# expander8.net
KiCad netlist of a schematic drawn in EAGLE
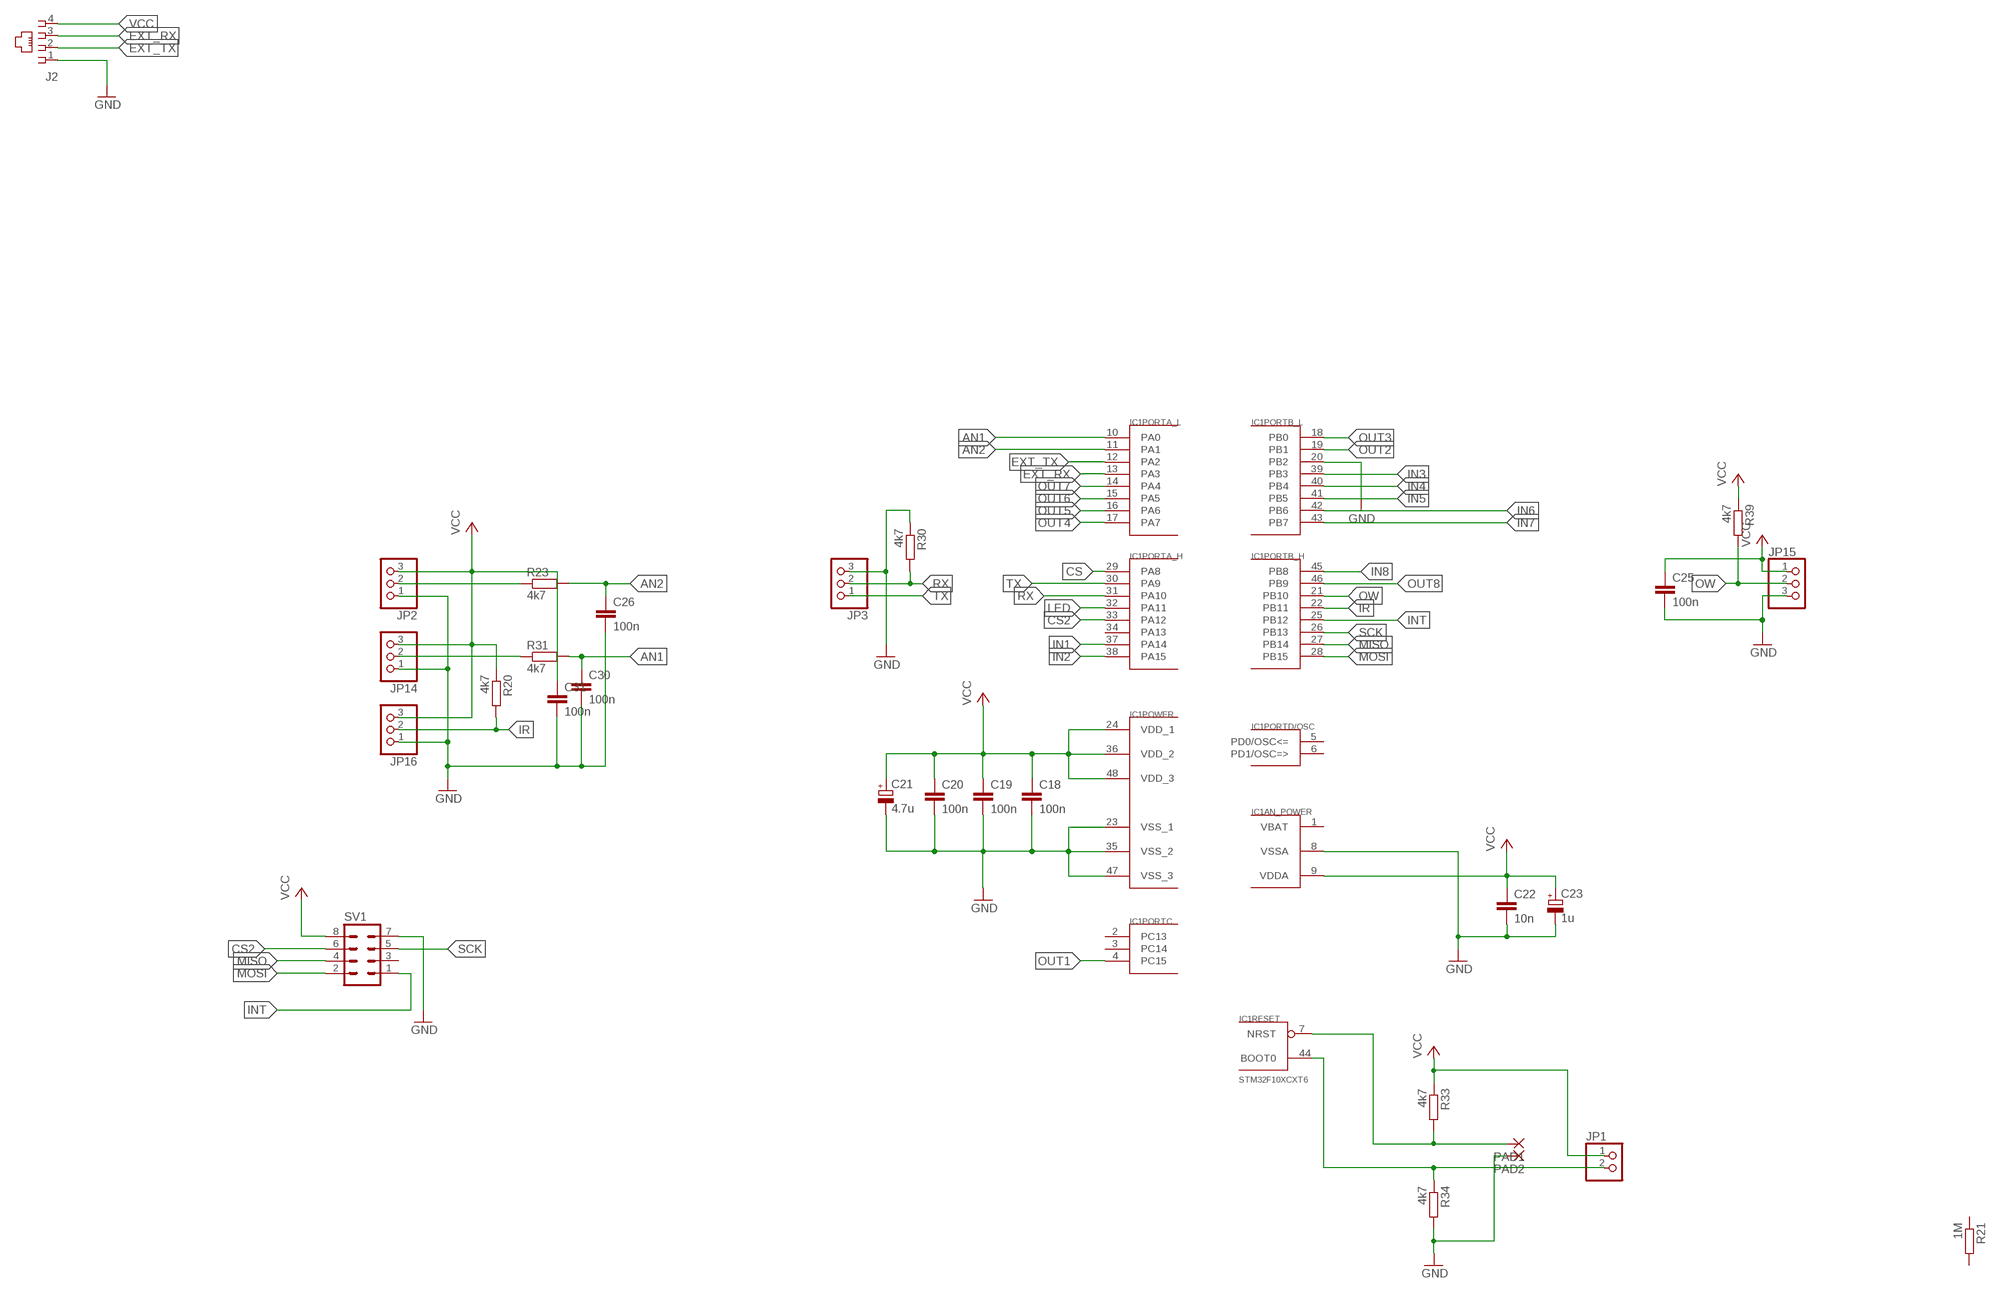
[diagram p0: schematic, sheet 1, part 1 of 3]
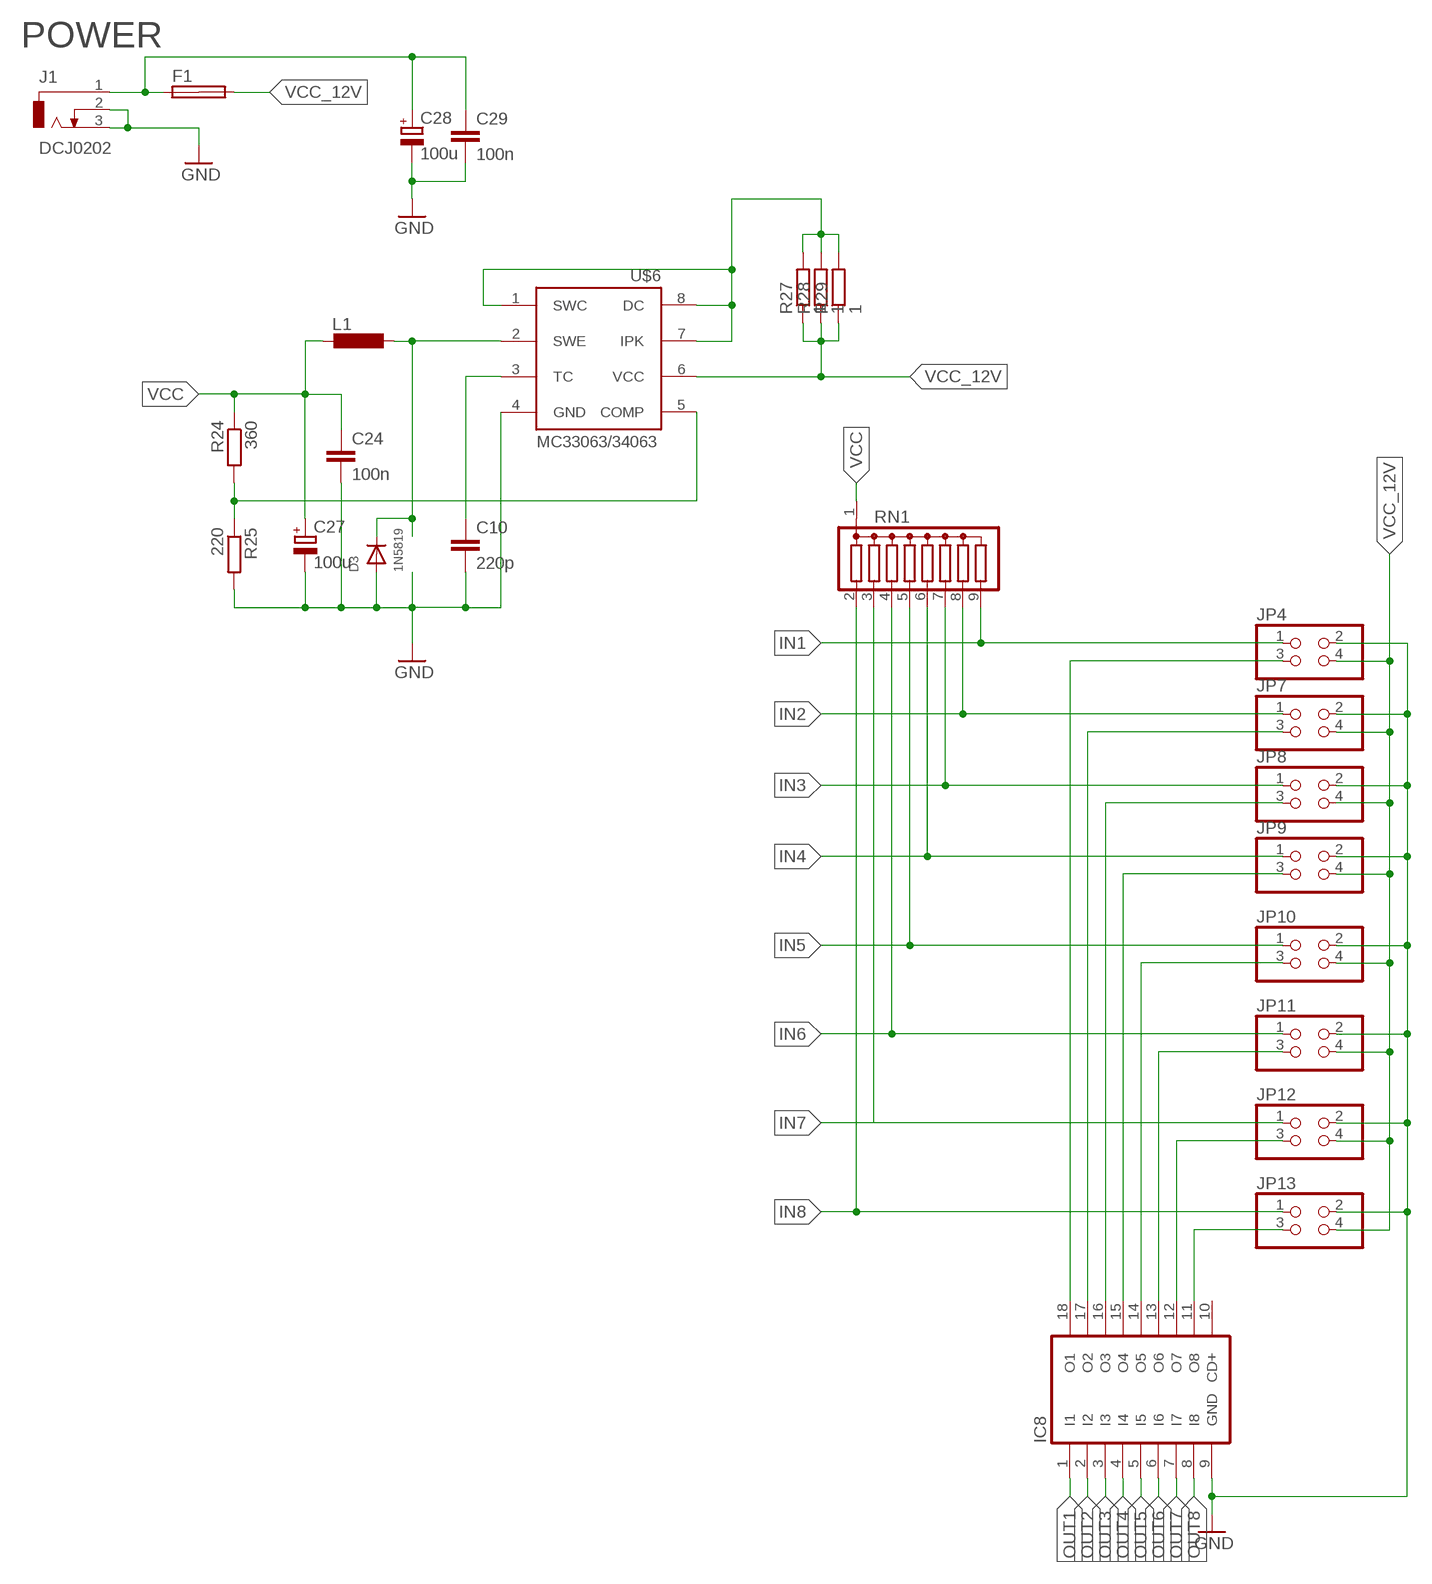
[diagram p1: schematic, sheet 1, part 2 of 3]
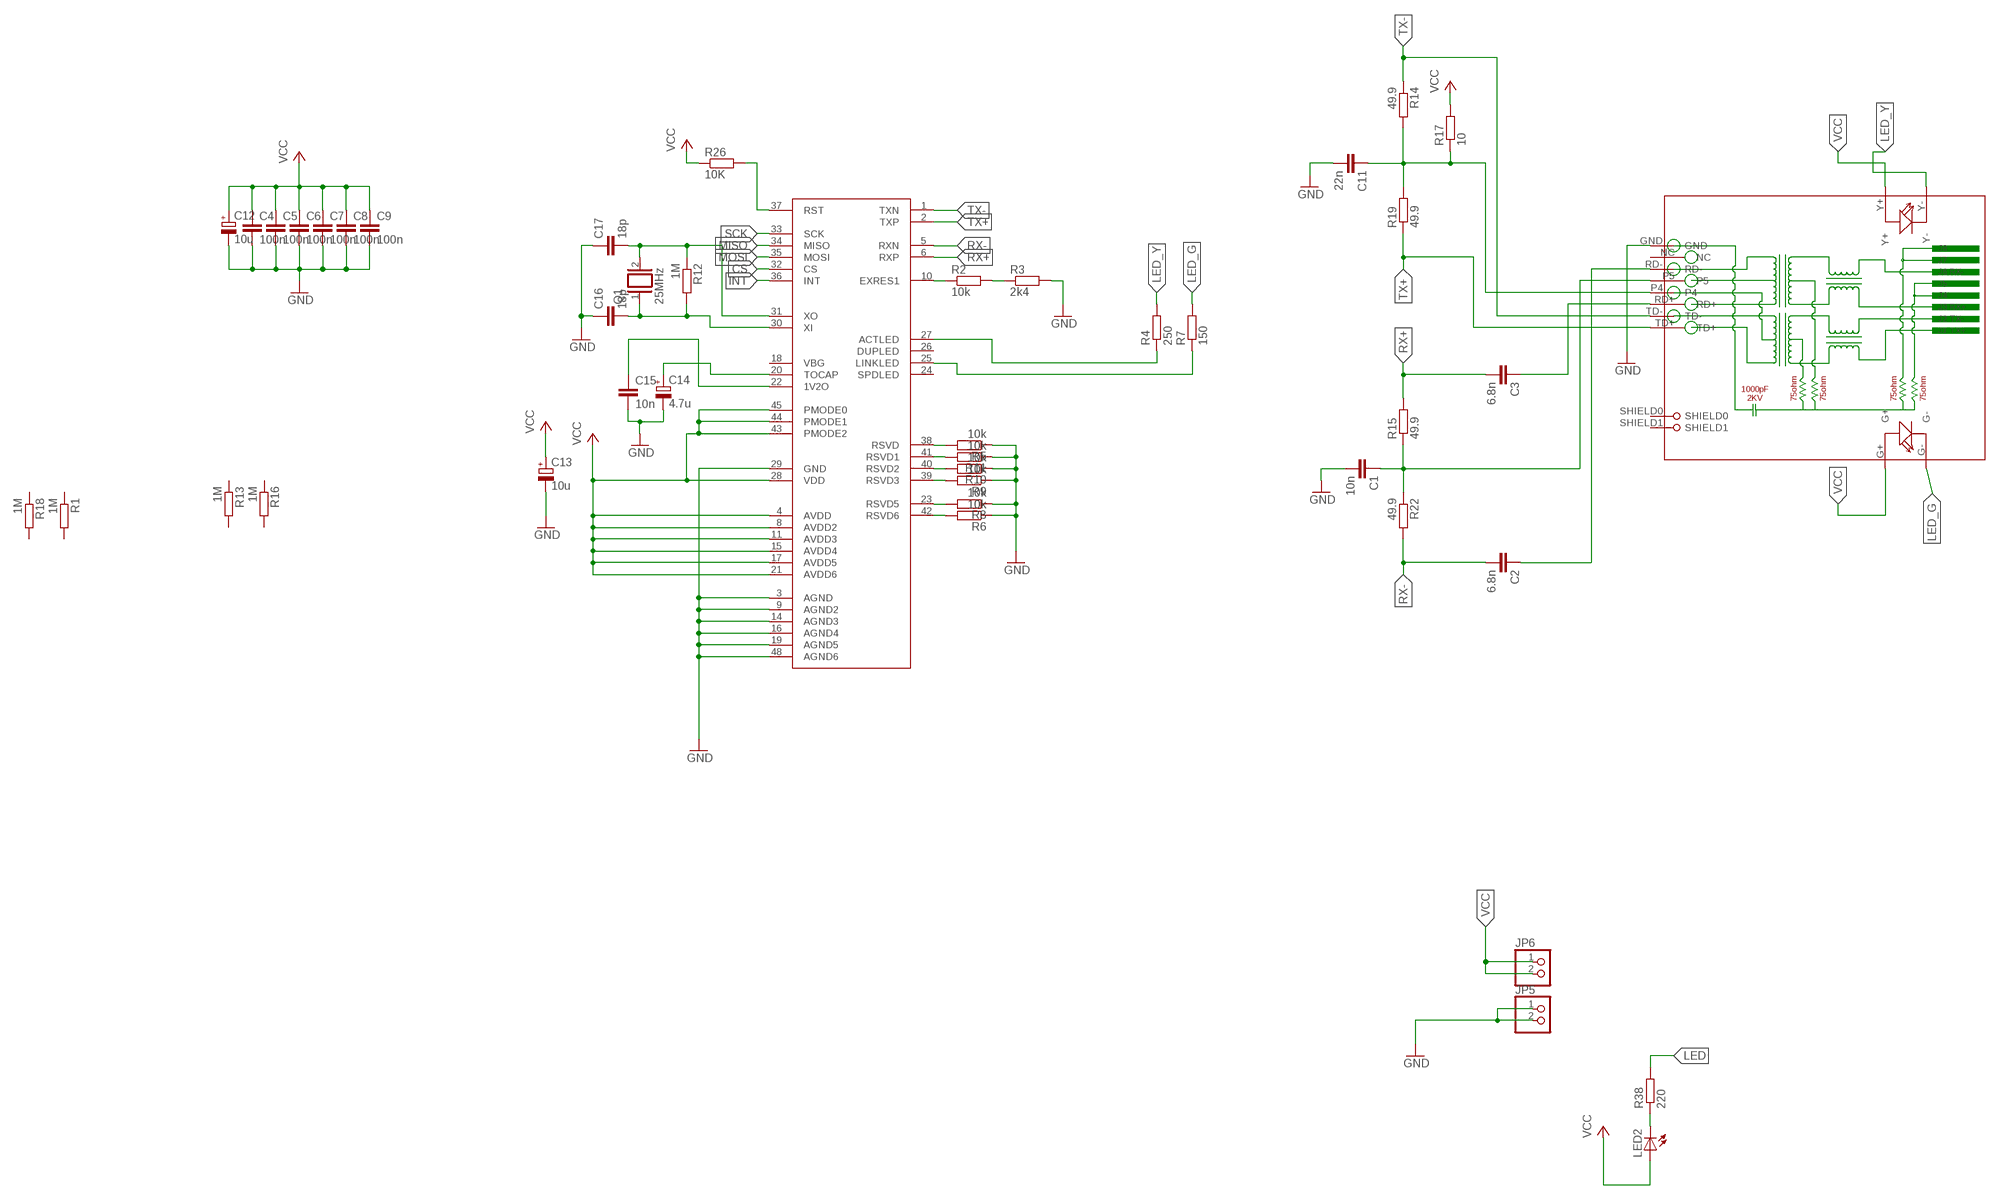
[diagram p2: schematic, sheet 1, part 3 of 3]

(export (version "E")
  (design (tool "Eeschema 10.0.6"))
  (components
    (comp (ref "C1")
      (value "10n")
      (footprint "eagle-import:C0805")
      (libsource (lib "eagle-import") (part "resistor_C-EUC0805"))
    )
    (comp (ref "C2")
      (value "6.8n")
      (footprint "eagle-import:C0805")
      (libsource (lib "eagle-import") (part "resistor_C-EUC0805"))
    )
    (comp (ref "C3")
      (value "6.8n")
      (footprint "eagle-import:C0805")
      (libsource (lib "eagle-import") (part "resistor_C-EUC0805"))
    )
    (comp (ref "C4")
      (value "100n")
      (footprint "eagle-import:C0805")
      (libsource (lib "eagle-import") (part "C-EUC0805"))
    )
    (comp (ref "C5")
      (value "100n")
      (footprint "eagle-import:C0805")
      (libsource (lib "eagle-import") (part "C-EUC0805"))
    )
    (comp (ref "C6")
      (value "100n")
      (footprint "eagle-import:C0805")
      (libsource (lib "eagle-import") (part "C-EUC0805"))
    )
    (comp (ref "C7")
      (value "100n")
      (footprint "eagle-import:C0805")
      (libsource (lib "eagle-import") (part "C-EUC0805"))
    )
    (comp (ref "C8")
      (value "100n")
      (footprint "eagle-import:C0805")
      (libsource (lib "eagle-import") (part "C-EUC0805"))
    )
    (comp (ref "C9")
      (value "100n")
      (footprint "eagle-import:C0805")
      (libsource (lib "eagle-import") (part "C-EUC0805"))
    )
    (comp (ref "C10")
      (value "220p")
      (footprint "eagle-import:C0805")
      (libsource (lib "eagle-import") (part "C-EUC0805"))
    )
    (comp (ref "C11")
      (value "22n")
      (footprint "eagle-import:C0805")
      (libsource (lib "eagle-import") (part "resistor_C-EUC0805"))
    )
    (comp (ref "C12")
      (value "10u")
      (footprint "eagle-import:E2,5-5")
      (libsource (lib "eagle-import") (part "CPOL-EUE2.5-5"))
    )
    (comp (ref "C13")
      (value "10u")
      (footprint "eagle-import:E2,5-5")
      (libsource (lib "eagle-import") (part "CPOL-EUE2.5-5"))
    )
    (comp (ref "C14")
      (value "4.7u")
      (footprint "eagle-import:E2,5-5")
      (libsource (lib "eagle-import") (part "CPOL-EUE2.5-5"))
    )
    (comp (ref "C15")
      (value "10n")
      (footprint "eagle-import:C1206")
      (libsource (lib "eagle-import") (part "C-EUC1206"))
    )
    (comp (ref "C16")
      (value "18p")
      (footprint "eagle-import:C0805")
      (libsource (lib "eagle-import") (part "C-EUC0805"))
    )
    (comp (ref "C17")
      (value "18p")
      (footprint "eagle-import:C0805")
      (libsource (lib "eagle-import") (part "C-EUC0805"))
    )
    (comp (ref "C18")
      (value "100n")
      (footprint "eagle-import:C0805")
      (libsource (lib "eagle-import") (part "C-EUC0805"))
    )
    (comp (ref "C19")
      (value "100n")
      (footprint "eagle-import:C0805")
      (libsource (lib "eagle-import") (part "C-EUC0805"))
    )
    (comp (ref "C20")
      (value "100n")
      (footprint "eagle-import:C0805")
      (libsource (lib "eagle-import") (part "C-EUC0805"))
    )
    (comp (ref "C21")
      (value "4.7u")
      (footprint "eagle-import:E2,5-5")
      (libsource (lib "eagle-import") (part "CPOL-EUE2.5-5"))
    )
    (comp (ref "C22")
      (value "10n")
      (footprint "eagle-import:C0805")
      (libsource (lib "eagle-import") (part "C-EUC0805"))
    )
    (comp (ref "C23")
      (value "1u")
      (footprint "eagle-import:E2,5-5")
      (libsource (lib "eagle-import") (part "CPOL-EUE2.5-5"))
    )
    (comp (ref "C24")
      (value "100n")
      (footprint "eagle-import:C0805")
      (libsource (lib "eagle-import") (part "C-EUC0805"))
    )
    (comp (ref "C25")
      (value "100n")
      (footprint "eagle-import:C1206")
      (libsource (lib "eagle-import") (part "resistor_C-EUC1206"))
    )
    (comp (ref "C26")
      (value "100n")
      (footprint "eagle-import:C0805")
      (libsource (lib "eagle-import") (part "C-EUC0805"))
    )
    (comp (ref "C27")
      (value "100u")
      (footprint "eagle-import:E2,5-7")
      (libsource (lib "eagle-import") (part "CPOL-EUE2.5-7"))
    )
    (comp (ref "C28")
      (value "100u")
      (footprint "eagle-import:E2,5-7")
      (libsource (lib "eagle-import") (part "CPOL-EUE2.5-7"))
    )
    (comp (ref "C29")
      (value "100n")
      (footprint "eagle-import:C0805")
      (libsource (lib "eagle-import") (part "C-EUC0805"))
    )
    (comp (ref "C30")
      (value "100n")
      (footprint "eagle-import:C1206")
      (libsource (lib "eagle-import") (part "C-EUC1206"))
    )
    (comp (ref "C31")
      (value "100n")
      (footprint "eagle-import:C0805")
      (libsource (lib "eagle-import") (part "C-EUC0805"))
    )
    (comp (ref "D3")
      (value "1N5819")
      (footprint "eagle-import:SMADIODE")
      (libsource (lib "eagle-import") (part "DIODESMA"))
    )
    (comp (ref "F1")
      (value "SHK20L")
      (footprint "eagle-import:SHK20L")
      (libsource (lib "eagle-import") (part "SHK20L"))
    )
    (comp (ref "IC1")
      (value "STM32F10XCXT6")
      (footprint "eagle-import:TQFP48")
      (libsource (lib "eagle-import") (part "STM32F10XCXT6"))
    )
    (comp (ref "IC8")
      (value "ULN2803AD")
      (footprint "eagle-import:SO18W")
      (libsource (lib "eagle-import") (part "ULN2803AD"))
    )
    (comp (ref "J1")
      (value "DCJ0202")
      (footprint "eagle-import:DCJ0202")
      (libsource (lib "eagle-import") (part "DCJ0202"))
    )
    (comp (ref "J2")
      (value "520250-2")
      (footprint "eagle-import:520250-2")
      (libsource (lib "eagle-import") (part "520250-2"))
    )
    (comp (ref "JP1")
      (value "PINHD-1X2")
      (footprint "eagle-import:1X02")
      (libsource (lib "eagle-import") (part "PINHD-1X2"))
    )
    (comp (ref "JP2")
      (value "PINHD-1X3")
      (footprint "eagle-import:1X03")
      (libsource (lib "eagle-import") (part "PINHD-1X3"))
    )
    (comp (ref "JP3")
      (value "PINHD-1X3")
      (footprint "eagle-import:1X03")
      (libsource (lib "eagle-import") (part "PINHD-1X3"))
    )
    (comp (ref "JP4")
      (value "PINHD-2X2/90")
      (footprint "eagle-import:2X02_90")
      (libsource (lib "eagle-import") (part "PINHD-2X2/90"))
    )
    (comp (ref "JP5")
      (value "PINHD-1X2")
      (footprint "eagle-import:1X02")
      (libsource (lib "eagle-import") (part "PINHD-1X2"))
    )
    (comp (ref "JP6")
      (value "PINHD-1X2")
      (footprint "eagle-import:1X02")
      (libsource (lib "eagle-import") (part "PINHD-1X2"))
    )
    (comp (ref "JP7")
      (value "PINHD-2X2/90")
      (footprint "eagle-import:2X02_90")
      (libsource (lib "eagle-import") (part "PINHD-2X2/90"))
    )
    (comp (ref "JP8")
      (value "PINHD-2X2/90")
      (footprint "eagle-import:2X02_90")
      (libsource (lib "eagle-import") (part "PINHD-2X2/90"))
    )
    (comp (ref "JP9")
      (value "PINHD-2X2/90")
      (footprint "eagle-import:2X02_90")
      (libsource (lib "eagle-import") (part "PINHD-2X2/90"))
    )
    (comp (ref "JP10")
      (value "PINHD-2X2/90")
      (footprint "eagle-import:2X02_90")
      (libsource (lib "eagle-import") (part "PINHD-2X2/90"))
    )
    (comp (ref "JP11")
      (value "PINHD-2X2/90")
      (footprint "eagle-import:2X02_90")
      (libsource (lib "eagle-import") (part "PINHD-2X2/90"))
    )
    (comp (ref "JP12")
      (value "PINHD-2X2/90")
      (footprint "eagle-import:2X02_90")
      (libsource (lib "eagle-import") (part "PINHD-2X2/90"))
    )
    (comp (ref "JP13")
      (value "PINHD-2X2/90")
      (footprint "eagle-import:2X02_90")
      (libsource (lib "eagle-import") (part "PINHD-2X2/90"))
    )
    (comp (ref "JP14")
      (value "PINHD-1X3")
      (footprint "eagle-import:1X03")
      (libsource (lib "eagle-import") (part "PINHD-1X3"))
    )
    (comp (ref "JP15")
      (value "PINHD-1X3")
      (footprint "eagle-import:1X03")
      (libsource (lib "eagle-import") (part "PINHD-1X3"))
    )
    (comp (ref "JP16")
      (value "PINHD-1X3")
      (footprint "eagle-import:1X03")
      (libsource (lib "eagle-import") (part "PINHD-1X3"))
    )
    (comp (ref "L1")
      (value "L-EU0207/2V")
      (footprint "eagle-import:0207_2V")
      (libsource (lib "eagle-import") (part "L-EU0207/2V"))
    )
    (comp (ref "LED2")
      (value "LEDCHIPLED_0805")
      (footprint "eagle-import:CHIPLED_0805")
      (libsource (lib "eagle-import") (part "LEDCHIPLED_0805"))
    )
    (comp (ref "PAD1")
      (value "SMD2")
      (footprint "eagle-import:SMD1,27-2,54")
      (libsource (lib "eagle-import") (part "SMD2"))
    )
    (comp (ref "PAD2")
      (value "SMD2")
      (footprint "eagle-import:SMD1,27-2,54")
      (libsource (lib "eagle-import") (part "SMD2"))
    )
    (comp (ref "Q1")
      (value "25MHz")
      (footprint "eagle-import:QS")
      (libsource (lib "eagle-import") (part "XTAL/S"))
    )
    (comp (ref "R1")
      (value "1M")
      (footprint "eagle-import:R1206")
      (libsource (lib "eagle-import") (part "rcl-kd_R-EU_R1206"))
    )
    (comp (ref "R2")
      (value "10k")
      (footprint "eagle-import:R0805")
      (libsource (lib "eagle-import") (part "rcl-kd_R-EU_R0805"))
    )
    (comp (ref "R3")
      (value "2k4")
      (footprint "eagle-import:R0805")
      (libsource (lib "eagle-import") (part "rcl-kd_R-EU_R0805"))
    )
    (comp (ref "R4")
      (value "250")
      (footprint "eagle-import:R1206")
      (libsource (lib "eagle-import") (part "rcl-kd_R-EU_R1206"))
    )
    (comp (ref "R5")
      (value "10k")
      (footprint "eagle-import:R0603")
      (libsource (lib "eagle-import") (part "rcl-kd_R-EU_R0603"))
    )
    (comp (ref "R6")
      (value "10k")
      (footprint "eagle-import:R0603")
      (libsource (lib "eagle-import") (part "rcl-kd_R-EU_R0603"))
    )
    (comp (ref "R7")
      (value "150")
      (footprint "eagle-import:R1206")
      (libsource (lib "eagle-import") (part "rcl-kd_R-EU_R1206"))
    )
    (comp (ref "R8")
      (value "10k")
      (footprint "eagle-import:R0805")
      (libsource (lib "eagle-import") (part "rcl-kd_R-EU_R0805"))
    )
    (comp (ref "R9")
      (value "10k")
      (footprint "eagle-import:R0603")
      (libsource (lib "eagle-import") (part "rcl-kd_R-EU_R0603"))
    )
    (comp (ref "R10")
      (value "10k")
      (footprint "eagle-import:R0603")
      (libsource (lib "eagle-import") (part "rcl-kd_R-EU_R0603"))
    )
    (comp (ref "R11")
      (value "10k")
      (footprint "eagle-import:R0603")
      (libsource (lib "eagle-import") (part "rcl-kd_R-EU_R0603"))
    )
    (comp (ref "R12")
      (value "1M")
      (footprint "eagle-import:R0805")
      (libsource (lib "eagle-import") (part "rcl-kd_R-EU_R0805"))
    )
    (comp (ref "R13")
      (value "1M")
      (footprint "eagle-import:R1206")
      (libsource (lib "eagle-import") (part "rcl-kd_R-EU_R1206"))
    )
    (comp (ref "R14")
      (value "49.9")
      (footprint "eagle-import:R0805")
      (libsource (lib "eagle-import") (part "resistor_R-EU_R0805"))
    )
    (comp (ref "R15")
      (value "49.9")
      (footprint "eagle-import:R1206")
      (libsource (lib "eagle-import") (part "resistor_R-EU_R1206"))
    )
    (comp (ref "R16")
      (value "1M")
      (footprint "eagle-import:R1206")
      (libsource (lib "eagle-import") (part "rcl-kd_R-EU_R1206"))
    )
    (comp (ref "R17")
      (value "10")
      (footprint "eagle-import:R0805")
      (libsource (lib "eagle-import") (part "resistor_R-EU_R0805"))
    )
    (comp (ref "R18")
      (value "1M")
      (footprint "eagle-import:R1206")
      (libsource (lib "eagle-import") (part "rcl-kd_R-EU_R1206"))
    )
    (comp (ref "R19")
      (value "49.9")
      (footprint "eagle-import:R1206")
      (libsource (lib "eagle-import") (part "resistor_R-EU_R1206"))
    )
    (comp (ref "R20")
      (value "4k7")
      (footprint "eagle-import:R0805")
      (libsource (lib "eagle-import") (part "resistor_R-EU_R0805"))
    )
    (comp (ref "R21")
      (value "1M")
      (footprint "eagle-import:R1206")
      (libsource (lib "eagle-import") (part "rcl-kd_R-EU_R1206"))
    )
    (comp (ref "R22")
      (value "49.9")
      (footprint "eagle-import:R0805")
      (libsource (lib "eagle-import") (part "resistor_R-EU_R0805"))
    )
    (comp (ref "R23")
      (value "4k7")
      (footprint "eagle-import:R0805")
      (libsource (lib "eagle-import") (part "resistor_R-EU_R0805"))
    )
    (comp (ref "R24")
      (value "360")
      (footprint "eagle-import:M1206")
      (libsource (lib "eagle-import") (part "R-EU_M1206"))
    )
    (comp (ref "R25")
      (value "220")
      (footprint "eagle-import:M1206")
      (libsource (lib "eagle-import") (part "R-EU_M1206"))
    )
    (comp (ref "R26")
      (value "10K")
      (footprint "eagle-import:R0805")
      (libsource (lib "eagle-import") (part "rcl-kd_R-EU_R0805"))
    )
    (comp (ref "R27")
      (value "1")
      (footprint "eagle-import:R1206")
      (libsource (lib "eagle-import") (part "rcl-kd_R-EU_R1206"))
    )
    (comp (ref "R28")
      (value "1")
      (footprint "eagle-import:R1206")
      (libsource (lib "eagle-import") (part "rcl-kd_R-EU_R1206"))
    )
    (comp (ref "R29")
      (value "1")
      (footprint "eagle-import:R1206")
      (libsource (lib "eagle-import") (part "rcl-kd_R-EU_R1206"))
    )
    (comp (ref "R30")
      (value "4k7")
      (footprint "eagle-import:R1206")
      (libsource (lib "eagle-import") (part "resistor_R-EU_R1206"))
    )
    (comp (ref "R31")
      (value "4k7")
      (footprint "eagle-import:R0805")
      (libsource (lib "eagle-import") (part "resistor_R-EU_R0805"))
    )
    (comp (ref "R33")
      (value "4k7")
      (footprint "eagle-import:R0805")
      (libsource (lib "eagle-import") (part "rcl-kd_R-EU_R0805"))
    )
    (comp (ref "R34")
      (value "4k7")
      (footprint "eagle-import:R1206")
      (libsource (lib "eagle-import") (part "rcl-kd_R-EU_R1206"))
    )
    (comp (ref "R38")
      (value "220")
      (footprint "eagle-import:R0805")
      (libsource (lib "eagle-import") (part "resistor_R-EU_R0805"))
    )
    (comp (ref "R39")
      (value "4k7")
      (footprint "eagle-import:R0805")
      (libsource (lib "eagle-import") (part "resistor_R-EU_R0805"))
    )
    (comp (ref "RJ1")
      (value "HR911105A")
      (footprint "eagle-import:HR911105A")
      (libsource (lib "eagle-import") (part "HR911105A"))
    )
    (comp (ref "RN1")
      (value "G08R")
      (footprint "eagle-import:SIL9")
      (libsource (lib "eagle-import") (part "G08R"))
    )
    (comp (ref "SV1")
      (value "MA04-2")
      (footprint "eagle-import:MA04-2")
      (libsource (lib "eagle-import") (part "MA04-2"))
    )
    (comp (ref "U$1")
      (value "W5500")
      (footprint "eagle-import:TQFP48")
      (libsource (lib "eagle-import") (part "W5500"))
    )
    (comp (ref "U$6")
      (value "MC33063/MC34063D")
      (footprint "eagle-import:SO08")
      (libsource (lib "eagle-import") (part "MC33063/MC34063D"))
    )
  )
  (nets
    (net (code "1") (name "/VBAT") (class "Default")
      (node (ref "IC1") (pin "1") (pinfunction "VBAT_1") (pintype "power_in"))
    )
    (net (code "2") (name "AN1") (class "Default")
      (node (ref "C30") (pin "1") (pinfunction "1_1") (pintype "passive"))
      (node (ref "IC1") (pin "10") (pinfunction "PA0_10") (pintype "bidirectional"))
      (node (ref "R31") (pin "2") (pinfunction "2_2") (pintype "passive"))
    )
    (net (code "3") (name "AN2") (class "Default")
      (node (ref "C26") (pin "1") (pinfunction "1_1") (pintype "passive"))
      (node (ref "IC1") (pin "11") (pinfunction "PA1_11") (pintype "bidirectional"))
      (node (ref "R23") (pin "2") (pinfunction "2_2") (pintype "passive"))
    )
    (net (code "4") (name "CS") (class "Default")
      (node (ref "IC1") (pin "29") (pinfunction "PA8_29") (pintype "bidirectional"))
      (node (ref "U$1") (pin "32") (pinfunction "CS_32") (pintype "bidirectional"))
    )
    (net (code "5") (name "CS2") (class "Default")
      (node (ref "IC1") (pin "33") (pinfunction "PA12_33") (pintype "bidirectional"))
      (node (ref "SV1") (pin "6") (pinfunction "6_6") (pintype "passive"))
    )
    (net (code "6") (name "EXT_RX") (class "Default")
      (node (ref "IC1") (pin "13") (pinfunction "PA3_13") (pintype "bidirectional"))
      (node (ref "J2") (pin "3") (pinfunction "3_3") (pintype "passive"))
    )
    (net (code "7") (name "EXT_TX") (class "Default")
      (node (ref "IC1") (pin "12") (pinfunction "PA2_12") (pintype "bidirectional"))
      (node (ref "J2") (pin "2") (pinfunction "2_2") (pintype "passive"))
    )
    (net (code "8") (name "GND") (class "Default")
      (node (ref "C1") (pin "2") (pinfunction "2_2") (pintype "passive"))
      (node (ref "C10") (pin "2") (pinfunction "2_2") (pintype "passive"))
      (node (ref "C11") (pin "2") (pinfunction "2_2") (pintype "passive"))
      (node (ref "C12") (pin "-") (pinfunction "-_-") (pintype "passive"))
      (node (ref "C13") (pin "-") (pinfunction "-_-") (pintype "passive"))
      (node (ref "C14") (pin "-") (pinfunction "-_-") (pintype "passive"))
      (node (ref "C15") (pin "2") (pinfunction "2_2") (pintype "passive"))
      (node (ref "C16") (pin "1") (pinfunction "1_1") (pintype "passive"))
      (node (ref "C17") (pin "1") (pinfunction "1_1") (pintype "passive"))
      (node (ref "C18") (pin "2") (pinfunction "2_2") (pintype "passive"))
      (node (ref "C19") (pin "2") (pinfunction "2_2") (pintype "passive"))
      (node (ref "C20") (pin "2") (pinfunction "2_2") (pintype "passive"))
      (node (ref "C21") (pin "-") (pinfunction "-_-") (pintype "passive"))
      (node (ref "C22") (pin "2") (pinfunction "2_2") (pintype "passive"))
      (node (ref "C23") (pin "-") (pinfunction "-_-") (pintype "passive"))
      (node (ref "C24") (pin "2") (pinfunction "2_2") (pintype "passive"))
      (node (ref "C25") (pin "2") (pinfunction "2_2") (pintype "passive"))
      (node (ref "C26") (pin "2") (pinfunction "2_2") (pintype "passive"))
      (node (ref "C27") (pin "-") (pinfunction "-_-") (pintype "passive"))
      (node (ref "C28") (pin "-") (pinfunction "-_-") (pintype "passive"))
      (node (ref "C29") (pin "2") (pinfunction "2_2") (pintype "passive"))
      (node (ref "C30") (pin "2") (pinfunction "2_2") (pintype "passive"))
      (node (ref "C31") (pin "2") (pinfunction "2_2") (pintype "passive"))
      (node (ref "C4") (pin "2") (pinfunction "2_2") (pintype "passive"))
      (node (ref "C5") (pin "2") (pinfunction "2_2") (pintype "passive"))
      (node (ref "C6") (pin "2") (pinfunction "2_2") (pintype "passive"))
      (node (ref "C7") (pin "2") (pinfunction "2_2") (pintype "passive"))
      (node (ref "C8") (pin "2") (pinfunction "2_2") (pintype "passive"))
      (node (ref "C9") (pin "2") (pinfunction "2_2") (pintype "passive"))
      (node (ref "D3") (pin "A") (pinfunction "A_A") (pintype "passive"))
      (node (ref "IC1") (pin "20") (pinfunction "PB2_20") (pintype "bidirectional"))
      (node (ref "IC1") (pin "23") (pinfunction "VSS_1_23") (pintype "power_in"))
      (node (ref "IC1") (pin "35") (pinfunction "VSS_2_35") (pintype "power_in"))
      (node (ref "IC1") (pin "47") (pinfunction "VSS_3_47") (pintype "power_in"))
      (node (ref "IC1") (pin "8") (pinfunction "VSSA_8") (pintype "power_in"))
      (node (ref "IC8") (pin "9") (pinfunction "GND_9") (pintype "power_in"))
      (node (ref "J1") (pin "2") (pinfunction "2_2") (pintype "passive"))
      (node (ref "J1") (pin "3") (pinfunction "3_3") (pintype "passive"))
      (node (ref "J2") (pin "1") (pinfunction "1_1") (pintype "passive"))
      (node (ref "JP10") (pin "2") (pinfunction "2_2") (pintype "passive"))
      (node (ref "JP11") (pin "2") (pinfunction "2_2") (pintype "passive"))
      (node (ref "JP12") (pin "2") (pinfunction "2_2") (pintype "passive"))
      (node (ref "JP13") (pin "2") (pinfunction "2_2") (pintype "passive"))
      (node (ref "JP14") (pin "1") (pinfunction "1_1") (pintype "passive"))
      (node (ref "JP15") (pin "3") (pinfunction "3_3") (pintype "passive"))
      (node (ref "JP16") (pin "1") (pinfunction "1_1") (pintype "passive"))
      (node (ref "JP2") (pin "1") (pinfunction "1_1") (pintype "passive"))
      (node (ref "JP3") (pin "3") (pinfunction "3_3") (pintype "passive"))
      (node (ref "JP4") (pin "2") (pinfunction "2_2") (pintype "passive"))
      (node (ref "JP5") (pin "1") (pinfunction "1_1") (pintype "passive"))
      (node (ref "JP5") (pin "2") (pinfunction "2_2") (pintype "passive"))
      (node (ref "JP7") (pin "2") (pinfunction "2_2") (pintype "passive"))
      (node (ref "JP8") (pin "2") (pinfunction "2_2") (pintype "passive"))
      (node (ref "JP9") (pin "2") (pinfunction "2_2") (pintype "passive"))
      (node (ref "PAD2") (pin "1") (pinfunction "P_1") (pintype "passive"))
      (node (ref "R10") (pin "1") (pinfunction "1_1") (pintype "passive"))
      (node (ref "R11") (pin "1") (pinfunction "1_1") (pintype "passive"))
      (node (ref "R25") (pin "2") (pinfunction "2_2") (pintype "passive"))
      (node (ref "R3") (pin "2") (pinfunction "2_2") (pintype "passive"))
      (node (ref "R30") (pin "1") (pinfunction "1_1") (pintype "passive"))
      (node (ref "R34") (pin "2") (pinfunction "2_2") (pintype "passive"))
      (node (ref "R5") (pin "1") (pinfunction "1_1") (pintype "passive"))
      (node (ref "R6") (pin "1") (pinfunction "1_1") (pintype "passive"))
      (node (ref "R8") (pin "1") (pinfunction "1_1") (pintype "passive"))
      (node (ref "R9") (pin "1") (pinfunction "1_1") (pintype "passive"))
      (node (ref "RJ1") (pin "GND") (pinfunction "GND_GND") (pintype "bidirectional"))
      (node (ref "SV1") (pin "7") (pinfunction "7_7") (pintype "passive"))
      (node (ref "U$1") (pin "14") (pinfunction "AGND3_14") (pintype "bidirectional"))
      (node (ref "U$1") (pin "16") (pinfunction "AGND4_16") (pintype "bidirectional"))
      (node (ref "U$1") (pin "19") (pinfunction "AGND5_19") (pintype "bidirectional"))
      (node (ref "U$1") (pin "29") (pinfunction "GND_29") (pintype "bidirectional"))
      (node (ref "U$1") (pin "3") (pinfunction "AGND_3") (pintype "bidirectional"))
      (node (ref "U$1") (pin "48") (pinfunction "AGND6_48") (pintype "bidirectional"))
      (node (ref "U$1") (pin "9") (pinfunction "AGND2_9") (pintype "bidirectional"))
      (node (ref "U$6") (pin "4") (pinfunction "GND_4") (pintype "power_in"))
    )
    (net (code "9") (name "IN1") (class "Default")
      (node (ref "IC1") (pin "37") (pinfunction "PA14_37") (pintype "bidirectional"))
      (node (ref "JP4") (pin "1") (pinfunction "1_1") (pintype "passive"))
      (node (ref "RN1") (pin "9") (pinfunction "9_9") (pintype "passive"))
    )
    (net (code "10") (name "IN2") (class "Default")
      (node (ref "IC1") (pin "38") (pinfunction "PA15_38") (pintype "bidirectional"))
      (node (ref "JP7") (pin "1") (pinfunction "1_1") (pintype "passive"))
      (node (ref "RN1") (pin "8") (pinfunction "8_8") (pintype "passive"))
    )
    (net (code "11") (name "IN3") (class "Default")
      (node (ref "IC1") (pin "39") (pinfunction "PB3_39") (pintype "bidirectional"))
      (node (ref "JP8") (pin "1") (pinfunction "1_1") (pintype "passive"))
      (node (ref "RN1") (pin "7") (pinfunction "7_7") (pintype "passive"))
    )
    (net (code "12") (name "IN4") (class "Default")
      (node (ref "IC1") (pin "40") (pinfunction "PB4_40") (pintype "bidirectional"))
      (node (ref "JP9") (pin "1") (pinfunction "1_1") (pintype "passive"))
      (node (ref "RN1") (pin "6") (pinfunction "6_6") (pintype "passive"))
    )
    (net (code "13") (name "IN5") (class "Default")
      (node (ref "IC1") (pin "41") (pinfunction "PB5_41") (pintype "bidirectional"))
      (node (ref "JP10") (pin "1") (pinfunction "1_1") (pintype "passive"))
      (node (ref "RN1") (pin "5") (pinfunction "5_5") (pintype "passive"))
    )
    (net (code "14") (name "IN6") (class "Default")
      (node (ref "IC1") (pin "42") (pinfunction "PB6_42") (pintype "bidirectional"))
      (node (ref "JP11") (pin "1") (pinfunction "1_1") (pintype "passive"))
      (node (ref "RN1") (pin "4") (pinfunction "4_4") (pintype "passive"))
    )
    (net (code "15") (name "IN7") (class "Default")
      (node (ref "IC1") (pin "43") (pinfunction "PB7_43") (pintype "bidirectional"))
      (node (ref "JP12") (pin "1") (pinfunction "1_1") (pintype "passive"))
      (node (ref "RN1") (pin "3") (pinfunction "3_3") (pintype "passive"))
    )
    (net (code "16") (name "IN8") (class "Default")
      (node (ref "IC1") (pin "45") (pinfunction "PB8_45") (pintype "bidirectional"))
      (node (ref "JP13") (pin "1") (pinfunction "1_1") (pintype "passive"))
      (node (ref "RN1") (pin "2") (pinfunction "2_2") (pintype "passive"))
    )
    (net (code "17") (name "INT") (class "Default")
      (node (ref "IC1") (pin "25") (pinfunction "PB12_25") (pintype "bidirectional"))
      (node (ref "SV1") (pin "1") (pinfunction "1_1") (pintype "passive"))
      (node (ref "U$1") (pin "36") (pinfunction "INT_36") (pintype "bidirectional"))
    )
    (net (code "18") (name "IR") (class "Default")
      (node (ref "IC1") (pin "22") (pinfunction "PB11_22") (pintype "bidirectional"))
      (node (ref "JP16") (pin "2") (pinfunction "2_2") (pintype "passive"))
      (node (ref "R20") (pin "2") (pinfunction "2_2") (pintype "passive"))
    )
    (net (code "19") (name "LED") (class "Default")
      (node (ref "IC1") (pin "32") (pinfunction "PA11_32") (pintype "bidirectional"))
      (node (ref "R38") (pin "2") (pinfunction "2_2") (pintype "passive"))
    )
    (net (code "20") (name "LED_G") (class "Default")
      (node (ref "R7") (pin "2") (pinfunction "2_2") (pintype "passive"))
      (node (ref "RJ1") (pin "G-") (pinfunction "G-_G-") (pintype "bidirectional"))
    )
    (net (code "21") (name "LED_Y") (class "Default")
      (node (ref "R4") (pin "2") (pinfunction "2_2") (pintype "passive"))
      (node (ref "RJ1") (pin "Y-") (pinfunction "Y-_Y-") (pintype "bidirectional"))
    )
    (net (code "22") (name "MISO") (class "Default")
      (node (ref "IC1") (pin "27") (pinfunction "PB14_27") (pintype "bidirectional"))
      (node (ref "SV1") (pin "4") (pinfunction "4_4") (pintype "passive"))
      (node (ref "U$1") (pin "34") (pinfunction "MISO_34") (pintype "bidirectional"))
    )
    (net (code "23") (name "MOSI") (class "Default")
      (node (ref "IC1") (pin "28") (pinfunction "PB15_28") (pintype "bidirectional"))
      (node (ref "SV1") (pin "2") (pinfunction "2_2") (pintype "passive"))
      (node (ref "U$1") (pin "35") (pinfunction "MOSI_35") (pintype "bidirectional"))
    )
    (net (code "24") (name "Net-(C1-Pad1)") (class "Default")
      (node (ref "C1") (pin "1") (pinfunction "1_1") (pintype "passive"))
      (node (ref "R15") (pin "1") (pinfunction "1_1") (pintype "passive"))
      (node (ref "R22") (pin "1") (pinfunction "1_1") (pintype "passive"))
      (node (ref "RJ1") (pin "P5") (pinfunction "P5_P5") (pintype "bidirectional"))
    )
    (net (code "25") (name "Net-(C2-Pad1)") (class "Default")
      (node (ref "C2") (pin "1") (pinfunction "1_1") (pintype "passive"))
      (node (ref "RJ1") (pin "RD-") (pinfunction "RD-_RD-") (pintype "bidirectional"))
    )
    (net (code "26") (name "Net-(C3-Pad1)") (class "Default")
      (node (ref "C3") (pin "1") (pinfunction "1_1") (pintype "passive"))
      (node (ref "RJ1") (pin "RD+") (pinfunction "RD+_RD+") (pintype "bidirectional"))
    )
    (net (code "27") (name "Net-(C11-Pad1)") (class "Default")
      (node (ref "C11") (pin "1") (pinfunction "1_1") (pintype "passive"))
      (node (ref "R14") (pin "2") (pinfunction "2_2") (pintype "passive"))
      (node (ref "R17") (pin "1") (pinfunction "1_1") (pintype "passive"))
      (node (ref "R19") (pin "2") (pinfunction "2_2") (pintype "passive"))
      (node (ref "RJ1") (pin "P4") (pinfunction "P4_P4") (pintype "bidirectional"))
    )
    (net (code "28") (name "Net-(C28-Pad+)") (class "Default")
      (node (ref "C28") (pin "+") (pinfunction "+_+") (pintype "passive"))
      (node (ref "C29") (pin "1") (pinfunction "1_1") (pintype "passive"))
      (node (ref "F1") (pin "1A") (pinfunction "1A_1A") (pintype "passive"))
      (node (ref "J1") (pin "1") (pinfunction "1_1") (pintype "passive"))
    )
    (net (code "29") (name "Net-(IC1I-BOOT0)") (class "Default")
      (node (ref "IC1") (pin "44") (pinfunction "BOOT0_44") (pintype "input"))
      (node (ref "JP1") (pin "2") (pinfunction "2_2") (pintype "passive"))
      (node (ref "R34") (pin "1") (pinfunction "1_1") (pintype "passive"))
    )
    (net (code "30") (name "Net-(IC1I-NRST)") (class "Default")
      (node (ref "IC1") (pin "7") (pinfunction "NRST_7") (pintype "input"))
      (node (ref "PAD1") (pin "1") (pinfunction "P_1") (pintype "passive"))
      (node (ref "R33") (pin "2") (pinfunction "2_2") (pintype "passive"))
    )
    (net (code "31") (name "Net-(IC8-O1)") (class "Default")
      (node (ref "IC8") (pin "18") (pinfunction "O1_18") (pintype "open_collector"))
      (node (ref "JP4") (pin "3") (pinfunction "3_3") (pintype "passive"))
    )
    (net (code "32") (name "Net-(IC8-O2)") (class "Default")
      (node (ref "IC8") (pin "17") (pinfunction "O2_17") (pintype "open_collector"))
      (node (ref "JP7") (pin "3") (pinfunction "3_3") (pintype "passive"))
    )
    (net (code "33") (name "Net-(IC8-O3)") (class "Default")
      (node (ref "IC8") (pin "16") (pinfunction "O3_16") (pintype "open_collector"))
      (node (ref "JP8") (pin "3") (pinfunction "3_3") (pintype "passive"))
    )
    (net (code "34") (name "Net-(IC8-O4)") (class "Default")
      (node (ref "IC8") (pin "15") (pinfunction "O4_15") (pintype "open_collector"))
      (node (ref "JP9") (pin "3") (pinfunction "3_3") (pintype "passive"))
    )
    (net (code "35") (name "Net-(IC8-O5)") (class "Default")
      (node (ref "IC8") (pin "14") (pinfunction "O5_14") (pintype "open_collector"))
      (node (ref "JP10") (pin "3") (pinfunction "3_3") (pintype "passive"))
    )
    (net (code "36") (name "Net-(IC8-O6)") (class "Default")
      (node (ref "IC8") (pin "13") (pinfunction "O6_13") (pintype "open_collector"))
      (node (ref "JP11") (pin "3") (pinfunction "3_3") (pintype "passive"))
    )
    (net (code "37") (name "Net-(IC8-O7)") (class "Default")
      (node (ref "IC8") (pin "12") (pinfunction "O7_12") (pintype "open_collector"))
      (node (ref "JP12") (pin "3") (pinfunction "3_3") (pintype "passive"))
    )
    (net (code "38") (name "Net-(IC8-O8)") (class "Default")
      (node (ref "IC8") (pin "11") (pinfunction "O8_11") (pintype "open_collector"))
      (node (ref "JP13") (pin "3") (pinfunction "3_3") (pintype "passive"))
    )
    (net (code "39") (name "Net-(JP2-Pad2)") (class "Default")
      (node (ref "JP2") (pin "2") (pinfunction "2_2") (pintype "passive"))
      (node (ref "R23") (pin "1") (pinfunction "1_1") (pintype "passive"))
    )
    (net (code "40") (name "Net-(JP14-Pad2)") (class "Default")
      (node (ref "JP14") (pin "2") (pinfunction "2_2") (pintype "passive"))
      (node (ref "R31") (pin "1") (pinfunction "1_1") (pintype "passive"))
    )
    (net (code "41") (name "Net-(LED2-PadC)") (class "Default")
      (node (ref "LED2") (pin "C") (pinfunction "C_C") (pintype "passive"))
      (node (ref "R38") (pin "1") (pinfunction "1_1") (pintype "passive"))
    )
    (net (code "42") (name "Net-(R2-Pad2)") (class "Default")
      (node (ref "R2") (pin "2") (pinfunction "2_2") (pintype "passive"))
      (node (ref "R3") (pin "1") (pinfunction "1_1") (pintype "passive"))
    )
    (net (code "43") (name "Net-(U$1-1V2O)") (class "Default")
      (node (ref "C15") (pin "1") (pinfunction "1_1") (pintype "passive"))
      (node (ref "U$1") (pin "22") (pinfunction "1V2O_22") (pintype "bidirectional"))
    )
    (net (code "44") (name "Net-(U$1-ACTLED)") (class "Default")
      (node (ref "R4") (pin "1") (pinfunction "1_1") (pintype "passive"))
      (node (ref "U$1") (pin "27") (pinfunction "ACTLED_27") (pintype "bidirectional"))
    )
    (net (code "45") (name "Net-(U$1-EXRES1)") (class "Default")
      (node (ref "R2") (pin "1") (pinfunction "1_1") (pintype "passive"))
      (node (ref "U$1") (pin "10") (pinfunction "EXRES1_10") (pintype "bidirectional"))
    )
    (net (code "46") (name "Net-(U$1-LINKLED)") (class "Default")
      (node (ref "R7") (pin "1") (pinfunction "1_1") (pintype "passive"))
      (node (ref "U$1") (pin "25") (pinfunction "LINKLED_25") (pintype "bidirectional"))
    )
    (net (code "47") (name "Net-(U$1-RST)") (class "Default")
      (node (ref "R26") (pin "2") (pinfunction "2_2") (pintype "passive"))
      (node (ref "U$1") (pin "37") (pinfunction "RST_37") (pintype "bidirectional"))
    )
    (net (code "48") (name "Net-(U$1-RSVD)") (class "Default")
      (node (ref "R5") (pin "2") (pinfunction "2_2") (pintype "passive"))
      (node (ref "U$1") (pin "38") (pinfunction "RSVD_38") (pintype "bidirectional"))
    )
    (net (code "49") (name "Net-(U$1-RSVD1)") (class "Default")
      (node (ref "R11") (pin "2") (pinfunction "2_2") (pintype "passive"))
      (node (ref "U$1") (pin "41") (pinfunction "RSVD1_41") (pintype "bidirectional"))
    )
    (net (code "50") (name "Net-(U$1-RSVD2)") (class "Default")
      (node (ref "R10") (pin "2") (pinfunction "2_2") (pintype "passive"))
      (node (ref "U$1") (pin "40") (pinfunction "RSVD2_40") (pintype "bidirectional"))
    )
    (net (code "51") (name "Net-(U$1-RSVD3)") (class "Default")
      (node (ref "R9") (pin "2") (pinfunction "2_2") (pintype "passive"))
      (node (ref "U$1") (pin "39") (pinfunction "RSVD3_39") (pintype "bidirectional"))
    )
    (net (code "52") (name "Net-(U$1-RSVD5)") (class "Default")
      (node (ref "R8") (pin "2") (pinfunction "2_2") (pintype "passive"))
      (node (ref "U$1") (pin "23") (pinfunction "RSVD5_23") (pintype "bidirectional"))
    )
    (net (code "53") (name "Net-(U$1-RSVD6)") (class "Default")
      (node (ref "R6") (pin "2") (pinfunction "2_2") (pintype "passive"))
      (node (ref "U$1") (pin "42") (pinfunction "RSVD6_42") (pintype "bidirectional"))
    )
    (net (code "54") (name "Net-(U$1-TOCAP)") (class "Default")
      (node (ref "C14") (pin "+") (pinfunction "+_+") (pintype "passive"))
      (node (ref "U$1") (pin "20") (pinfunction "TOCAP_20") (pintype "bidirectional"))
    )
    (net (code "55") (name "Net-(U$1-XI)") (class "Default")
      (node (ref "C16") (pin "2") (pinfunction "2_2") (pintype "passive"))
      (node (ref "Q1") (pin "1") (pinfunction "1_1") (pintype "passive"))
      (node (ref "R12") (pin "2") (pinfunction "2_2") (pintype "passive"))
      (node (ref "U$1") (pin "30") (pinfunction "XI_30") (pintype "bidirectional"))
    )
    (net (code "56") (name "Net-(U$1-XO)") (class "Default")
      (node (ref "C17") (pin "2") (pinfunction "2_2") (pintype "passive"))
      (node (ref "Q1") (pin "2") (pinfunction "2_2") (pintype "passive"))
      (node (ref "R12") (pin "1") (pinfunction "1_1") (pintype "passive"))
      (node (ref "U$1") (pin "31") (pinfunction "XO_31") (pintype "bidirectional"))
    )
    (net (code "57") (name "Net-(U$6-COMP)") (class "Default")
      (node (ref "R24") (pin "2") (pinfunction "2_2") (pintype "passive"))
      (node (ref "R25") (pin "1") (pinfunction "1_1") (pintype "passive"))
      (node (ref "U$6") (pin "5") (pinfunction "COMP_5") (pintype "input"))
    )
    (net (code "58") (name "Net-(U$6-DC)") (class "Default")
      (node (ref "R27") (pin "2") (pinfunction "2_2") (pintype "passive"))
      (node (ref "R28") (pin "2") (pinfunction "2_2") (pintype "passive"))
      (node (ref "R29") (pin "2") (pinfunction "2_2") (pintype "passive"))
      (node (ref "U$6") (pin "1") (pinfunction "SWC_1") (pintype "input"))
      (node (ref "U$6") (pin "7") (pinfunction "IPK_7") (pintype "bidirectional"))
      (node (ref "U$6") (pin "8") (pinfunction "DC_8") (pintype "input"))
    )
    (net (code "59") (name "Net-(U$6-SWE)") (class "Default")
      (node (ref "D3") (pin "C") (pinfunction "C_C") (pintype "passive"))
      (node (ref "L1") (pin "1") (pinfunction "1_1") (pintype "passive"))
      (node (ref "U$6") (pin "2") (pinfunction "SWE_2") (pintype "input"))
    )
    (net (code "60") (name "Net-(U$6-TC)") (class "Default")
      (node (ref "C10") (pin "1") (pinfunction "1_1") (pintype "passive"))
      (node (ref "U$6") (pin "3") (pinfunction "TC_3") (pintype "input"))
    )
    (net (code "61") (name "OUT1") (class "Default")
      (node (ref "IC1") (pin "4") (pinfunction "PC15_4") (pintype "bidirectional"))
      (node (ref "IC8") (pin "1") (pinfunction "I1_1") (pintype "input"))
    )
    (net (code "62") (name "OUT2") (class "Default")
      (node (ref "IC1") (pin "19") (pinfunction "PB1_19") (pintype "bidirectional"))
      (node (ref "IC8") (pin "2") (pinfunction "I2_2") (pintype "input"))
    )
    (net (code "63") (name "OUT3") (class "Default")
      (node (ref "IC1") (pin "18") (pinfunction "PB0_18") (pintype "bidirectional"))
      (node (ref "IC8") (pin "3") (pinfunction "I3_3") (pintype "input"))
    )
    (net (code "64") (name "OUT4") (class "Default")
      (node (ref "IC1") (pin "17") (pinfunction "PA7_17") (pintype "bidirectional"))
      (node (ref "IC8") (pin "4") (pinfunction "I4_4") (pintype "input"))
    )
    (net (code "65") (name "OUT5") (class "Default")
      (node (ref "IC1") (pin "16") (pinfunction "PA6_16") (pintype "bidirectional"))
      (node (ref "IC8") (pin "5") (pinfunction "I5_5") (pintype "input"))
    )
    (net (code "66") (name "OUT6") (class "Default")
      (node (ref "IC1") (pin "15") (pinfunction "PA5_15") (pintype "bidirectional"))
      (node (ref "IC8") (pin "6") (pinfunction "I6_6") (pintype "input"))
    )
    (net (code "67") (name "OUT7") (class "Default")
      (node (ref "IC1") (pin "14") (pinfunction "PA4_14") (pintype "bidirectional"))
      (node (ref "IC8") (pin "7") (pinfunction "I7_7") (pintype "input"))
    )
    (net (code "68") (name "OUT8") (class "Default")
      (node (ref "IC1") (pin "46") (pinfunction "PB9_46") (pintype "bidirectional"))
      (node (ref "IC8") (pin "8") (pinfunction "I8_8") (pintype "input"))
    )
    (net (code "69") (name "OW") (class "Default")
      (node (ref "IC1") (pin "21") (pinfunction "PB10_21") (pintype "bidirectional"))
      (node (ref "JP15") (pin "2") (pinfunction "2_2") (pintype "passive"))
      (node (ref "R39") (pin "2") (pinfunction "2_2") (pintype "passive"))
    )
    (net (code "70") (name "RX") (class "Default")
      (node (ref "IC1") (pin "31") (pinfunction "PA10_31") (pintype "bidirectional"))
      (node (ref "JP3") (pin "2") (pinfunction "2_2") (pintype "passive"))
      (node (ref "R30") (pin "2") (pinfunction "2_2") (pintype "passive"))
    )
    (net (code "71") (name "RX+") (class "Default")
      (node (ref "C3") (pin "2") (pinfunction "2_2") (pintype "passive"))
      (node (ref "R15") (pin "2") (pinfunction "2_2") (pintype "passive"))
      (node (ref "U$1") (pin "6") (pinfunction "RXP_6") (pintype "bidirectional"))
    )
    (net (code "72") (name "RX-") (class "Default")
      (node (ref "C2") (pin "2") (pinfunction "2_2") (pintype "passive"))
      (node (ref "R22") (pin "2") (pinfunction "2_2") (pintype "passive"))
      (node (ref "U$1") (pin "5") (pinfunction "RXN_5") (pintype "bidirectional"))
    )
    (net (code "73") (name "SCK") (class "Default")
      (node (ref "IC1") (pin "26") (pinfunction "PB13_26") (pintype "bidirectional"))
      (node (ref "SV1") (pin "5") (pinfunction "5_5") (pintype "passive"))
      (node (ref "U$1") (pin "33") (pinfunction "SCK_33") (pintype "bidirectional"))
    )
    (net (code "74") (name "TX") (class "Default")
      (node (ref "IC1") (pin "30") (pinfunction "PA9_30") (pintype "bidirectional"))
      (node (ref "JP3") (pin "1") (pinfunction "1_1") (pintype "passive"))
    )
    (net (code "75") (name "TX+") (class "Default")
      (node (ref "R19") (pin "1") (pinfunction "1_1") (pintype "passive"))
      (node (ref "RJ1") (pin "TD+") (pinfunction "TD+_TD+") (pintype "bidirectional"))
      (node (ref "U$1") (pin "2") (pinfunction "TXP_2") (pintype "bidirectional"))
    )
    (net (code "76") (name "TX-") (class "Default")
      (node (ref "R14") (pin "1") (pinfunction "1_1") (pintype "passive"))
      (node (ref "RJ1") (pin "TD-") (pinfunction "TD-_TD-") (pintype "bidirectional"))
      (node (ref "U$1") (pin "1") (pinfunction "TXN_1") (pintype "bidirectional"))
    )
    (net (code "77") (name "VCC") (class "Default")
      (node (ref "C12") (pin "+") (pinfunction "+_+") (pintype "passive"))
      (node (ref "C13") (pin "+") (pinfunction "+_+") (pintype "passive"))
      (node (ref "C18") (pin "1") (pinfunction "1_1") (pintype "passive"))
      (node (ref "C19") (pin "1") (pinfunction "1_1") (pintype "passive"))
      (node (ref "C20") (pin "1") (pinfunction "1_1") (pintype "passive"))
      (node (ref "C21") (pin "+") (pinfunction "+_+") (pintype "passive"))
      (node (ref "C22") (pin "1") (pinfunction "1_1") (pintype "passive"))
      (node (ref "C23") (pin "+") (pinfunction "+_+") (pintype "passive"))
      (node (ref "C24") (pin "1") (pinfunction "1_1") (pintype "passive"))
      (node (ref "C25") (pin "1") (pinfunction "1_1") (pintype "passive"))
      (node (ref "C27") (pin "+") (pinfunction "+_+") (pintype "passive"))
      (node (ref "C31") (pin "1") (pinfunction "1_1") (pintype "passive"))
      (node (ref "C4") (pin "1") (pinfunction "1_1") (pintype "passive"))
      (node (ref "C5") (pin "1") (pinfunction "1_1") (pintype "passive"))
      (node (ref "C6") (pin "1") (pinfunction "1_1") (pintype "passive"))
      (node (ref "C7") (pin "1") (pinfunction "1_1") (pintype "passive"))
      (node (ref "C8") (pin "1") (pinfunction "1_1") (pintype "passive"))
      (node (ref "C9") (pin "1") (pinfunction "1_1") (pintype "passive"))
      (node (ref "IC1") (pin "24") (pinfunction "VDD_1_24") (pintype "power_in"))
      (node (ref "IC1") (pin "36") (pinfunction "VDD_2_36") (pintype "power_in"))
      (node (ref "IC1") (pin "48") (pinfunction "VDD_3_48") (pintype "power_in"))
      (node (ref "IC1") (pin "9") (pinfunction "VDDA_9") (pintype "power_in"))
      (node (ref "J2") (pin "4") (pinfunction "4_4") (pintype "passive"))
      (node (ref "JP1") (pin "1") (pinfunction "1_1") (pintype "passive"))
      (node (ref "JP14") (pin "3") (pinfunction "3_3") (pintype "passive"))
      (node (ref "JP15") (pin "1") (pinfunction "1_1") (pintype "passive"))
      (node (ref "JP16") (pin "3") (pinfunction "3_3") (pintype "passive"))
      (node (ref "JP2") (pin "3") (pinfunction "3_3") (pintype "passive"))
      (node (ref "JP6") (pin "1") (pinfunction "1_1") (pintype "passive"))
      (node (ref "JP6") (pin "2") (pinfunction "2_2") (pintype "passive"))
      (node (ref "L1") (pin "2") (pinfunction "2_2") (pintype "passive"))
      (node (ref "LED2") (pin "A") (pinfunction "A_A") (pintype "passive"))
      (node (ref "R17") (pin "2") (pinfunction "2_2") (pintype "passive"))
      (node (ref "R20") (pin "1") (pinfunction "1_1") (pintype "passive"))
      (node (ref "R24") (pin "1") (pinfunction "1_1") (pintype "passive"))
      (node (ref "R26") (pin "1") (pinfunction "1_1") (pintype "passive"))
      (node (ref "R33") (pin "1") (pinfunction "1_1") (pintype "passive"))
      (node (ref "R39") (pin "1") (pinfunction "1_1") (pintype "passive"))
      (node (ref "RJ1") (pin "G+") (pinfunction "G+_G+") (pintype "bidirectional"))
      (node (ref "RJ1") (pin "Y+") (pinfunction "Y+_Y+") (pintype "bidirectional"))
      (node (ref "RN1") (pin "1") (pinfunction "1_1") (pintype "passive"))
      (node (ref "SV1") (pin "8") (pinfunction "8_8") (pintype "passive"))
      (node (ref "U$1") (pin "11") (pinfunction "AVDD3_11") (pintype "bidirectional"))
      (node (ref "U$1") (pin "15") (pinfunction "AVDD4_15") (pintype "bidirectional"))
      (node (ref "U$1") (pin "17") (pinfunction "AVDD5_17") (pintype "bidirectional"))
      (node (ref "U$1") (pin "21") (pinfunction "AVDD6_21") (pintype "bidirectional"))
      (node (ref "U$1") (pin "28") (pinfunction "VDD_28") (pintype "bidirectional"))
      (node (ref "U$1") (pin "4") (pinfunction "AVDD_4") (pintype "bidirectional"))
      (node (ref "U$1") (pin "43") (pinfunction "PMODE2_43") (pintype "bidirectional"))
      (node (ref "U$1") (pin "44") (pinfunction "PMODE1_44") (pintype "bidirectional"))
      (node (ref "U$1") (pin "45") (pinfunction "PMODE0_45") (pintype "bidirectional"))
      (node (ref "U$1") (pin "8") (pinfunction "AVDD2_8") (pintype "bidirectional"))
    )
    (net (code "78") (name "VCC_12V") (class "Default")
      (node (ref "F1") (pin "2A") (pinfunction "2A_2A") (pintype "passive"))
      (node (ref "JP10") (pin "4") (pinfunction "4_4") (pintype "passive"))
      (node (ref "JP11") (pin "4") (pinfunction "4_4") (pintype "passive"))
      (node (ref "JP12") (pin "4") (pinfunction "4_4") (pintype "passive"))
      (node (ref "JP13") (pin "4") (pinfunction "4_4") (pintype "passive"))
      (node (ref "JP4") (pin "4") (pinfunction "4_4") (pintype "passive"))
      (node (ref "JP7") (pin "4") (pinfunction "4_4") (pintype "passive"))
      (node (ref "JP8") (pin "4") (pinfunction "4_4") (pintype "passive"))
      (node (ref "JP9") (pin "4") (pinfunction "4_4") (pintype "passive"))
      (node (ref "R27") (pin "1") (pinfunction "1_1") (pintype "passive"))
      (node (ref "R28") (pin "1") (pinfunction "1_1") (pintype "passive"))
      (node (ref "R29") (pin "1") (pinfunction "1_1") (pintype "passive"))
      (node (ref "U$6") (pin "6") (pinfunction "VCC_6") (pintype "power_in"))
    )
    (net (code "79") (name "unconnected-(F1-Pad1B)") (class "Default")
      (node (ref "F1") (pin "1B") (pinfunction "1B_1B") (pintype "passive"))
    )
    (net (code "80") (name "unconnected-(F1-Pad2B)") (class "Default")
      (node (ref "F1") (pin "2B") (pinfunction "2B_2B") (pintype "passive"))
    )
    (net (code "81") (name "unconnected-(IC1B-PA13-Pad34)") (class "Default")
      (node (ref "IC1") (pin "34") (pinfunction "PA13_34") (pintype "bidirectional"))
    )
    (net (code "82") (name "unconnected-(IC1F-PC13-Pad2)") (class "Default")
      (node (ref "IC1") (pin "2") (pinfunction "PC13_2") (pintype "bidirectional"))
    )
    (net (code "83") (name "unconnected-(IC1F-PC14-Pad3)") (class "Default")
      (node (ref "IC1") (pin "3") (pinfunction "PC14_3") (pintype "bidirectional"))
    )
    (net (code "84") (name "unconnected-(IC1G-PD0{slash}OSC<=-Pad5)") (class "Default")
      (node (ref "IC1") (pin "5") (pinfunction "PD0/OSC<=_5") (pintype "bidirectional"))
    )
    (net (code "85") (name "unconnected-(IC1G-PD1{slash}OSC=>-Pad6)") (class "Default")
      (node (ref "IC1") (pin "6") (pinfunction "PD1/OSC=>_6") (pintype "bidirectional"))
    )
    (net (code "86") (name "unconnected-(IC8-CD+-Pad10)") (class "Default")
      (node (ref "IC8") (pin "10") (pinfunction "CD+_10") (pintype "passive"))
    )
    (net (code "87") (name "unconnected-(R1-Pad1)") (class "Default")
      (node (ref "R1") (pin "1") (pinfunction "1_1") (pintype "passive"))
    )
    (net (code "88") (name "unconnected-(R1-Pad2)") (class "Default")
      (node (ref "R1") (pin "2") (pinfunction "2_2") (pintype "passive"))
    )
    (net (code "89") (name "unconnected-(R13-Pad1)") (class "Default")
      (node (ref "R13") (pin "1") (pinfunction "1_1") (pintype "passive"))
    )
    (net (code "90") (name "unconnected-(R13-Pad2)") (class "Default")
      (node (ref "R13") (pin "2") (pinfunction "2_2") (pintype "passive"))
    )
    (net (code "91") (name "unconnected-(R16-Pad1)") (class "Default")
      (node (ref "R16") (pin "1") (pinfunction "1_1") (pintype "passive"))
    )
    (net (code "92") (name "unconnected-(R16-Pad2)") (class "Default")
      (node (ref "R16") (pin "2") (pinfunction "2_2") (pintype "passive"))
    )
    (net (code "93") (name "unconnected-(R18-Pad1)") (class "Default")
      (node (ref "R18") (pin "1") (pinfunction "1_1") (pintype "passive"))
    )
    (net (code "94") (name "unconnected-(R18-Pad2)") (class "Default")
      (node (ref "R18") (pin "2") (pinfunction "2_2") (pintype "passive"))
    )
    (net (code "95") (name "unconnected-(R21-Pad1)") (class "Default")
      (node (ref "R21") (pin "1") (pinfunction "1_1") (pintype "passive"))
    )
    (net (code "96") (name "unconnected-(R21-Pad2)") (class "Default")
      (node (ref "R21") (pin "2") (pinfunction "2_2") (pintype "passive"))
    )
    (net (code "97") (name "unconnected-(RJ1-PadNC)") (class "Default")
      (node (ref "RJ1") (pin "NC") (pinfunction "NC_NC") (pintype "bidirectional"))
    )
    (net (code "98") (name "unconnected-(RJ1-PadSHIELD0)") (class "Default")
      (node (ref "RJ1") (pin "SHIELD0") (pinfunction "SHIELD0_SHIELD0") (pintype "bidirectional"))
    )
    (net (code "99") (name "unconnected-(RJ1-PadSHIELD1)") (class "Default")
      (node (ref "RJ1") (pin "SHIELD1") (pinfunction "SHIELD1_SHIELD1") (pintype "bidirectional"))
    )
    (net (code "100") (name "unconnected-(SV1-Pad3)") (class "Default")
      (node (ref "SV1") (pin "3") (pinfunction "3_3") (pintype "passive"))
    )
    (net (code "101") (name "unconnected-(U$1-DUPLED-Pad26)") (class "Default")
      (node (ref "U$1") (pin "26") (pinfunction "DUPLED_26") (pintype "bidirectional"))
    )
    (net (code "102") (name "unconnected-(U$1-SPDLED-Pad24)") (class "Default")
      (node (ref "U$1") (pin "24") (pinfunction "SPDLED_24") (pintype "bidirectional"))
    )
    (net (code "103") (name "unconnected-(U$1-VBG-Pad18)") (class "Default")
      (node (ref "U$1") (pin "18") (pinfunction "VBG_18") (pintype "bidirectional"))
    )
  )
)
